# USB-C-Breakout.net
KiCad netlist of a schematic drawn in EAGLE
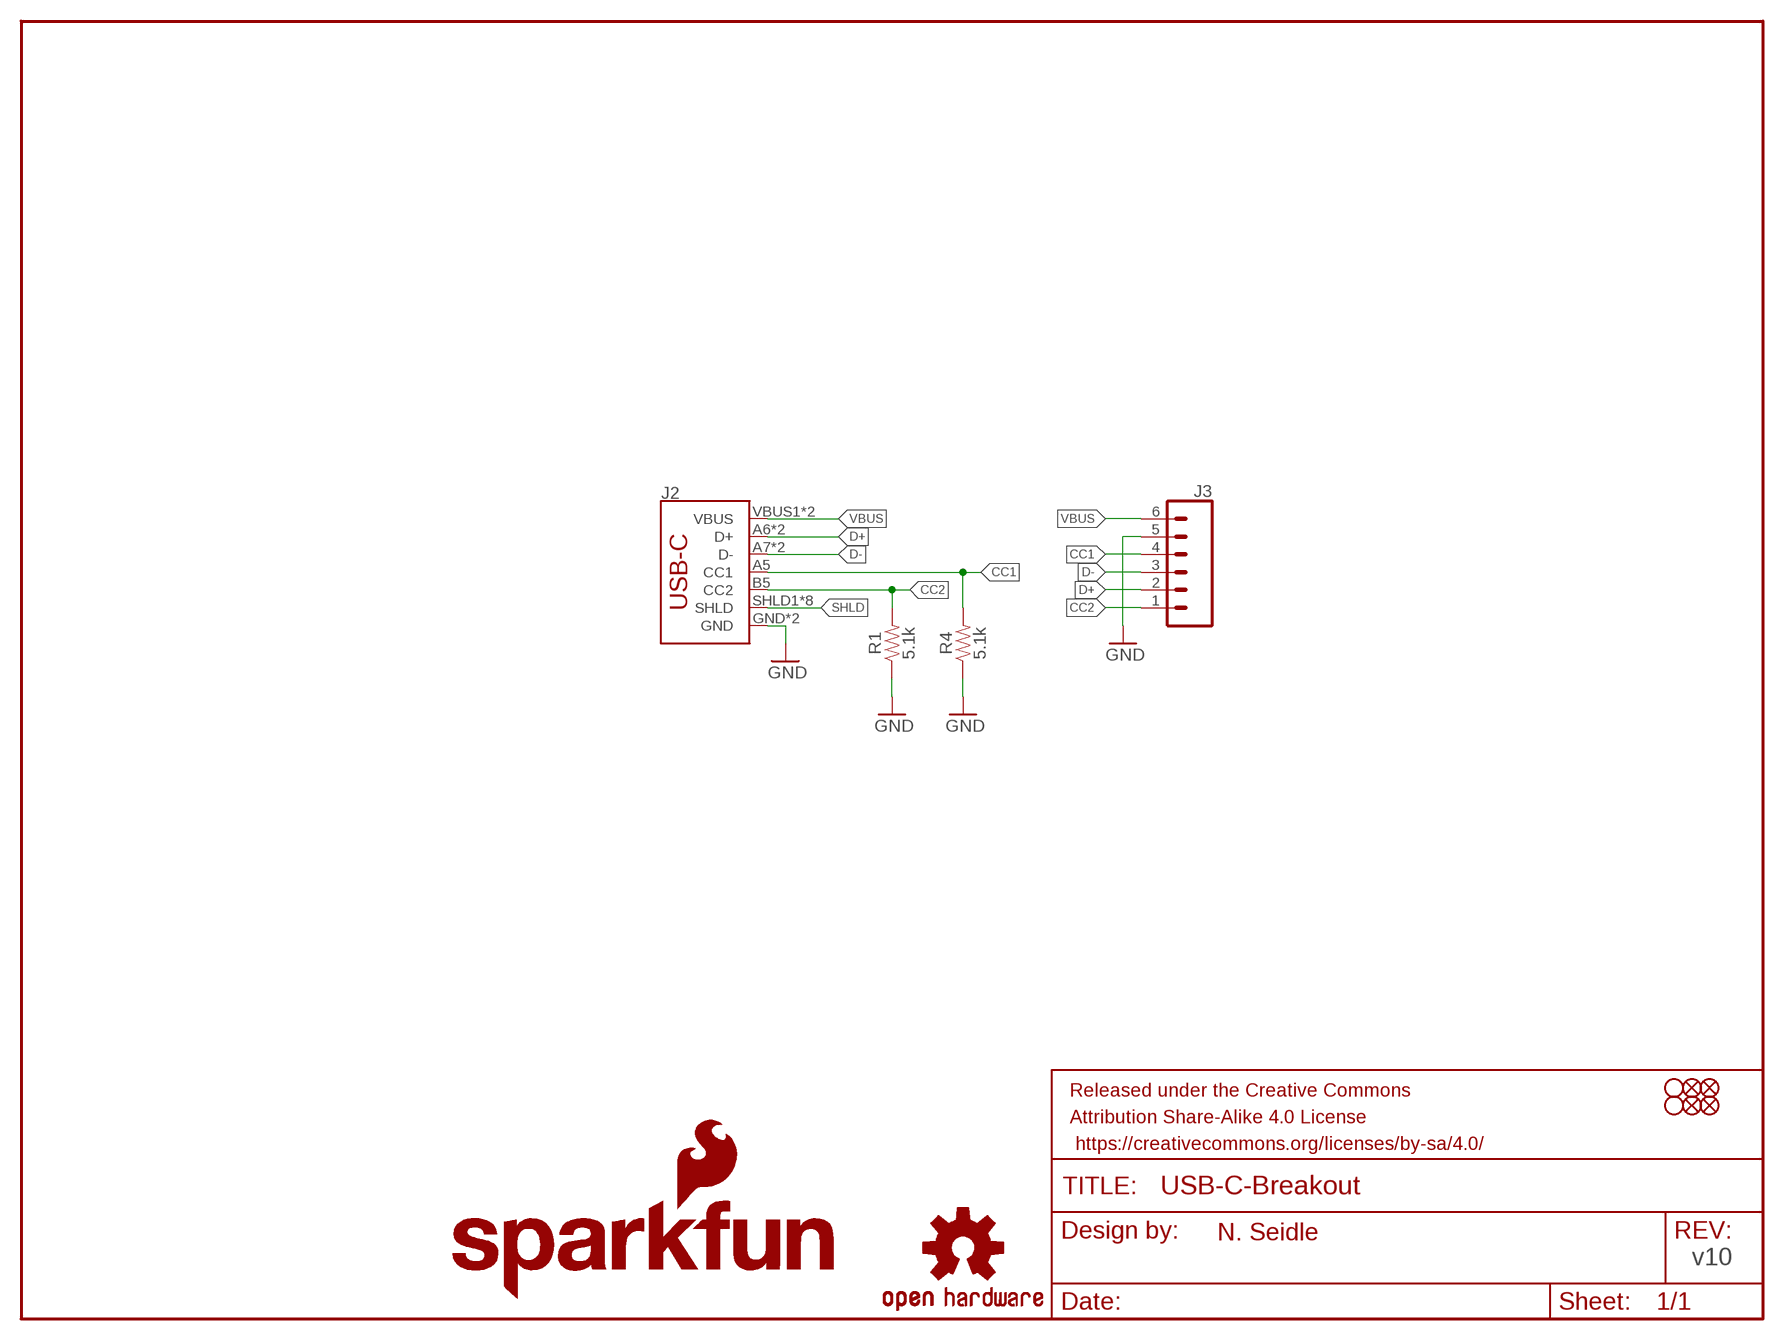
[diagram p0: schematic, sheet 1]

(export (version "E")
  (design (tool "Eeschema 10.0.6"))
  (components
    (comp (ref "FRAME1")
      (value "FRAME-LETTER")
      (footprint "eagle-import:CREATIVE_COMMONS")
      (libsource (lib "eagle-import") (part "FRAME-LETTER"))
    )
    (comp (ref "H1")
      (value "STAND-OFF")
      (footprint "eagle-import:STAND-OFF")
      (libsource (lib "eagle-import") (part "STAND-OFF"))
    )
    (comp (ref "H2")
      (value "STAND-OFF")
      (footprint "eagle-import:STAND-OFF")
      (libsource (lib "eagle-import") (part "STAND-OFF"))
    )
    (comp (ref "J2")
      (value "USB_C16PIN")
      (footprint "eagle-import:USB-C-16P")
      (libsource (lib "eagle-import") (part "USB_C16PIN"))
    )
    (comp (ref "J3")
      (value "CONN_06NO_SILK_NO_POP")
      (footprint "eagle-import:1X06_NO_SILK")
      (libsource (lib "eagle-import") (part "CONN_06NO_SILK_NO_POP"))
    )
    (comp (ref "JP3")
      (value "FIDUCIAL1X2")
      (footprint "eagle-import:FIDUCIAL-1X2")
      (libsource (lib "eagle-import") (part "FIDUCIAL1X2"))
    )
    (comp (ref "JP4")
      (value "FIDUCIAL1X2")
      (footprint "eagle-import:FIDUCIAL-1X2")
      (libsource (lib "eagle-import") (part "FIDUCIAL1X2"))
    )
    (comp (ref "JP5")
      (value "FIDUCIAL1X2")
      (footprint "eagle-import:FIDUCIAL-1X2")
      (libsource (lib "eagle-import") (part "FIDUCIAL1X2"))
    )
    (comp (ref "JP6")
      (value "FIDUCIAL1X2")
      (footprint "eagle-import:FIDUCIAL-1X2")
      (libsource (lib "eagle-import") (part "FIDUCIAL1X2"))
    )
    (comp (ref "LOGO1")
      (value "OSHW-LOGOS")
      (footprint "eagle-import:OSHW-LOGO-S")
      (libsource (lib "eagle-import") (part "OSHW-LOGOS"))
    )
    (comp (ref "LOGO2")
      (value "SFE_LOGO_FLAME.1_INCH")
      (footprint "eagle-import:SFE_LOGO_FLAME_.1")
      (libsource (lib "eagle-import") (part "SFE_LOGO_FLAME.1_INCH"))
    )
    (comp (ref "LOGO4")
      (value "SFE_LOGO_NAME_FLAME.1_INCH")
      (footprint "eagle-import:SFE_LOGO_NAME_FLAME_.1")
      (libsource (lib "eagle-import") (part "SFE_LOGO_NAME_FLAME.1_INCH"))
    )
    (comp (ref "R1")
      (value "5.1k")
      (footprint "eagle-import:0603")
      (libsource (lib "eagle-import") (part "5.1KOHM5.1KOHM-0603-1/10W-1%"))
    )
    (comp (ref "R4")
      (value "5.1k")
      (footprint "eagle-import:0603")
      (libsource (lib "eagle-import") (part "5.1KOHM5.1KOHM-0603-1/10W-1%"))
    )
  )
  (nets
    (net (code "1") (name "CC1") (class "Default")
      (node (ref "J2") (pin "A5") (pinfunction "CC1_A5") (pintype "bidirectional"))
      (node (ref "J3") (pin "4") (pinfunction "4_4") (pintype "passive"))
      (node (ref "R4") (pin "2") (pinfunction "2_2") (pintype "passive"))
    )
    (net (code "2") (name "CC2") (class "Default")
      (node (ref "J2") (pin "B5") (pinfunction "CC2_B5") (pintype "bidirectional"))
      (node (ref "J3") (pin "1") (pinfunction "1_1") (pintype "passive"))
      (node (ref "R1") (pin "2") (pinfunction "2_2") (pintype "passive"))
    )
    (net (code "3") (name "D+") (class "Default")
      (node (ref "J2") (pin "A6") (pinfunction "D+_A6") (pintype "bidirectional"))
      (node (ref "J2") (pin "B6") (pinfunction "D+_B6") (pintype "bidirectional"))
      (node (ref "J3") (pin "2") (pinfunction "2_2") (pintype "passive"))
    )
    (net (code "4") (name "D-") (class "Default")
      (node (ref "J2") (pin "A7") (pinfunction "D-_A7") (pintype "bidirectional"))
      (node (ref "J2") (pin "B7") (pinfunction "D-_B7") (pintype "bidirectional"))
      (node (ref "J3") (pin "3") (pinfunction "3_3") (pintype "passive"))
    )
    (net (code "5") (name "GND") (class "Default")
      (node (ref "J2") (pin "GND") (pinfunction "GND_GND") (pintype "bidirectional"))
      (node (ref "J2") (pin "GND2") (pinfunction "GND_GND2") (pintype "bidirectional"))
      (node (ref "J3") (pin "5") (pinfunction "5_5") (pintype "passive"))
      (node (ref "R1") (pin "1") (pinfunction "1_1") (pintype "passive"))
      (node (ref "R4") (pin "1") (pinfunction "1_1") (pintype "passive"))
    )
    (net (code "6") (name "SHLD") (class "Default")
      (node (ref "J2") (pin "SHLD1") (pinfunction "SHLD_SHLD1") (pintype "bidirectional"))
      (node (ref "J2") (pin "SHLD2") (pinfunction "SHLD_SHLD2") (pintype "bidirectional"))
      (node (ref "J2") (pin "SHLD3") (pinfunction "SHLD_SHLD3") (pintype "bidirectional"))
      (node (ref "J2") (pin "SHLD4") (pinfunction "SHLD_SHLD4") (pintype "bidirectional"))
      (node (ref "J2") (pin "SHLD5") (pinfunction "SHLD_SHLD5") (pintype "bidirectional"))
      (node (ref "J2") (pin "SHLD6") (pinfunction "SHLD_SHLD6") (pintype "bidirectional"))
      (node (ref "J2") (pin "SHLD7") (pinfunction "SHLD_SHLD7") (pintype "bidirectional"))
      (node (ref "J2") (pin "SHLD8") (pinfunction "SHLD_SHLD8") (pintype "bidirectional"))
    )
    (net (code "7") (name "VBUS") (class "Default")
      (node (ref "J2") (pin "VBUS1") (pinfunction "VBUS_VBUS1") (pintype "bidirectional"))
      (node (ref "J2") (pin "VBUS2") (pinfunction "VBUS_VBUS2") (pintype "bidirectional"))
      (node (ref "J3") (pin "6") (pinfunction "6_6") (pintype "passive"))
    )
  )
)
